# 2out_0-10V_2te.net
KiCad netlist of a schematic drawn in EAGLE
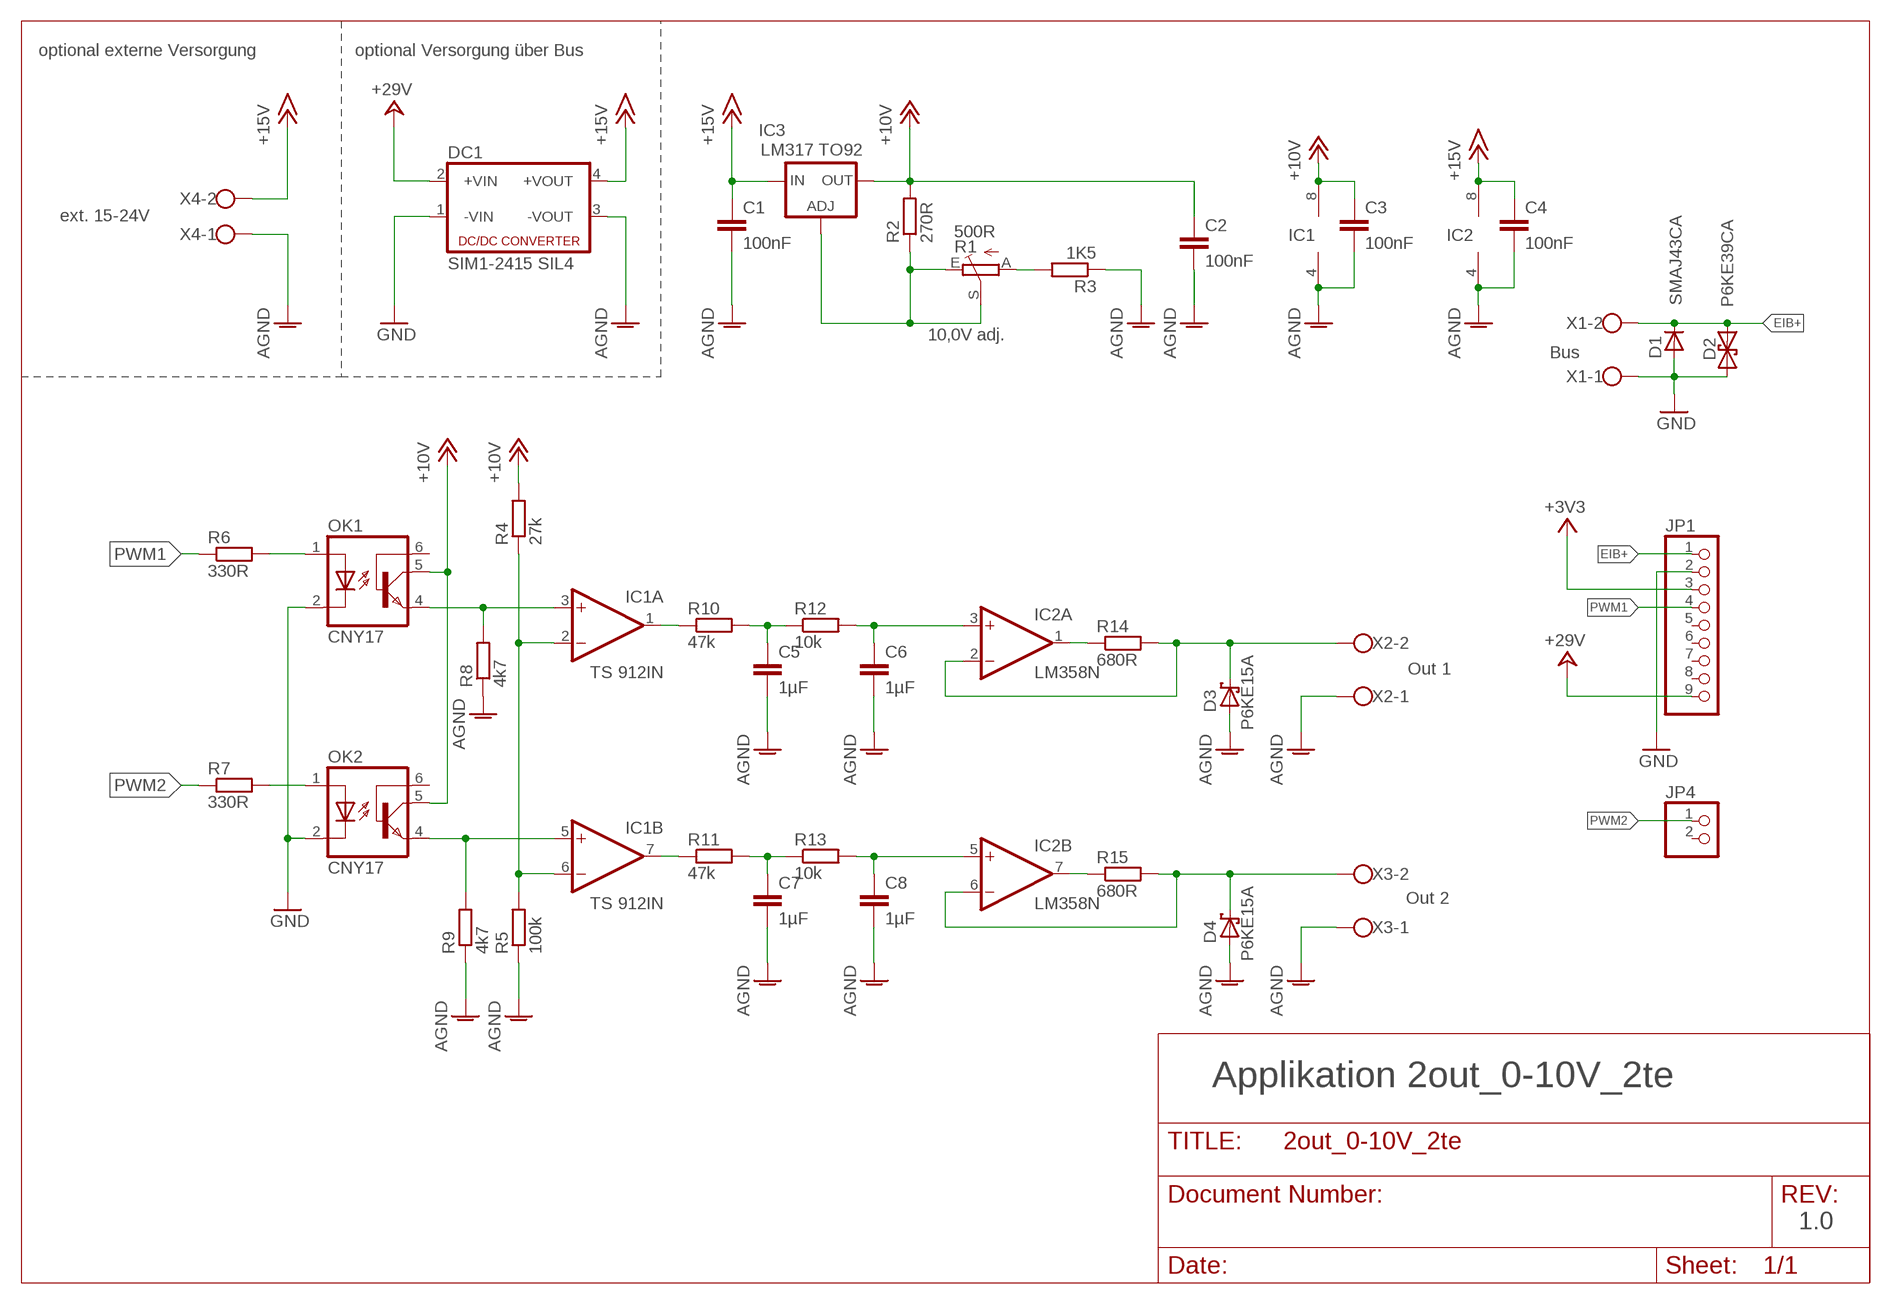
[diagram p0: schematic, sheet 1]

(export (version "E")
  (design (tool "Eeschema 10.0.6"))
  (components
    (comp (ref "C1")
      (value "100nF")
      (footprint "eagle-import:C025-024X044")
      (libsource (lib "eagle-import") (part "C-EU025-024X044"))
    )
    (comp (ref "C2")
      (value "100nF")
      (footprint "eagle-import:C025-024X044")
      (libsource (lib "eagle-import") (part "C-EU025-024X044"))
    )
    (comp (ref "C3")
      (value "100nF")
      (footprint "eagle-import:C025-024X044")
      (libsource (lib "eagle-import") (part "C-EU025-024X044"))
    )
    (comp (ref "C4")
      (value "100nF")
      (footprint "eagle-import:C025-024X044")
      (libsource (lib "eagle-import") (part "C-EU025-024X044"))
    )
    (comp (ref "C5")
      (value "1µF")
      (footprint "eagle-import:C050-024X044")
      (libsource (lib "eagle-import") (part "C-EU050-024X044"))
    )
    (comp (ref "C6")
      (value "1µF")
      (footprint "eagle-import:C050-024X044")
      (libsource (lib "eagle-import") (part "C-EU050-024X044"))
    )
    (comp (ref "C7")
      (value "1µF")
      (footprint "eagle-import:C050-024X044")
      (libsource (lib "eagle-import") (part "C-EU050-024X044"))
    )
    (comp (ref "C8")
      (value "1µF")
      (footprint "eagle-import:C050-024X044")
      (libsource (lib "eagle-import") (part "C-EU050-024X044"))
    )
    (comp (ref "D1")
      (value "SMAJ43CA")
      (footprint "eagle-import:SOD87")
      (libsource (lib "eagle-import") (part "D-SOD-87"))
    )
    (comp (ref "D2")
      (value "P6KE39CA")
      (footprint "eagle-import:DO41-7")
      (libsource (lib "eagle-import") (part "P6KEXXCDO41-7"))
    )
    (comp (ref "D3")
      (value "P6KE15A")
      (footprint "eagle-import:DO41-7")
      (libsource (lib "eagle-import") (part "P6KEXXADO41-7"))
    )
    (comp (ref "D4")
      (value "P6KE15A")
      (footprint "eagle-import:DO41-7")
      (libsource (lib "eagle-import") (part "P6KEXXADO41-7"))
    )
    (comp (ref "DC1")
      (value "SIM1-2415 SIL4")
      (footprint "eagle-import:NME")
      (libsource (lib "eagle-import") (part "NME"))
    )
    (comp (ref "IC1")
      (value "TS 912IN")
      (footprint "eagle-import:DIL08")
      (libsource (lib "eagle-import") (part "LM358N"))
    )
    (comp (ref "IC2")
      (value "LM358N")
      (footprint "eagle-import:DIL08")
      (libsource (lib "eagle-import") (part "LM358N"))
    )
    (comp (ref "IC3")
      (value "LM317 TO92")
      (footprint "eagle-import:317L")
      (libsource (lib "eagle-import") (part "LM317L"))
    )
    (comp (ref "JP1")
      (value "PINHD-1X9")
      (footprint "eagle-import:1X09")
      (libsource (lib "eagle-import") (part "PINHD-1X9"))
    )
    (comp (ref "JP4")
      (value "PINHD-1X2")
      (footprint "eagle-import:1X02")
      (libsource (lib "eagle-import") (part "PINHD-1X2"))
    )
    (comp (ref "OK1")
      (value "CNY17")
      (footprint "eagle-import:DIL06")
      (fields (field (name "MPN") "CNY17-1"))
      (libsource (lib "eagle-import") (part "CNY17"))
    )
    (comp (ref "OK2")
      (value "CNY17")
      (footprint "eagle-import:DIL06")
      (fields (field (name "MPN") "CNY17-1"))
      (libsource (lib "eagle-import") (part "CNY17"))
    )
    (comp (ref "R1")
      (value "500R")
      (footprint "eagle-import:B64W")
      (libsource (lib "eagle-import") (part "TRIM_EU-B64W"))
    )
    (comp (ref "R2")
      (value "270R")
      (footprint "eagle-import:0207_7")
      (libsource (lib "eagle-import") (part "R-EU_0207/7"))
    )
    (comp (ref "R3")
      (value "1K5")
      (footprint "eagle-import:0207_7")
      (libsource (lib "eagle-import") (part "R-EU_0207/7"))
    )
    (comp (ref "R4")
      (value "27k")
      (footprint "eagle-import:0207_7")
      (libsource (lib "eagle-import") (part "R-EU_0207/7"))
    )
    (comp (ref "R5")
      (value "100k")
      (footprint "eagle-import:0207_7")
      (libsource (lib "eagle-import") (part "R-EU_0207/7"))
    )
    (comp (ref "R6")
      (value "330R")
      (footprint "eagle-import:0207_7")
      (libsource (lib "eagle-import") (part "R-EU_0207/7"))
    )
    (comp (ref "R7")
      (value "330R")
      (footprint "eagle-import:0207_7")
      (libsource (lib "eagle-import") (part "R-EU_0207/7"))
    )
    (comp (ref "R8")
      (value "4k7")
      (footprint "eagle-import:0207_7")
      (libsource (lib "eagle-import") (part "R-EU_0207/7"))
    )
    (comp (ref "R9")
      (value "4k7")
      (footprint "eagle-import:0207_7")
      (libsource (lib "eagle-import") (part "R-EU_0207/7"))
    )
    (comp (ref "R10")
      (value "47k")
      (footprint "eagle-import:0207_7")
      (libsource (lib "eagle-import") (part "R-EU_0207/7"))
    )
    (comp (ref "R11")
      (value "47k")
      (footprint "eagle-import:0207_7")
      (libsource (lib "eagle-import") (part "R-EU_0207/7"))
    )
    (comp (ref "R12")
      (value "10k")
      (footprint "eagle-import:0207_7")
      (libsource (lib "eagle-import") (part "R-EU_0207/7"))
    )
    (comp (ref "R13")
      (value "10k")
      (footprint "eagle-import:0207_7")
      (libsource (lib "eagle-import") (part "R-EU_0207/7"))
    )
    (comp (ref "R14")
      (value "680R")
      (footprint "eagle-import:0207_7")
      (libsource (lib "eagle-import") (part "R-EU_0207/7"))
    )
    (comp (ref "R15")
      (value "680R")
      (footprint "eagle-import:0207_7")
      (libsource (lib "eagle-import") (part "R-EU_0207/7"))
    )
    (comp (ref "X1")
      (value "W237-02P")
      (footprint "eagle-import:W237-132")
      (libsource (lib "eagle-import") (part "W237-02P"))
    )
    (comp (ref "X2")
      (value "W237-02P")
      (footprint "eagle-import:W237-132")
      (libsource (lib "eagle-import") (part "W237-02P"))
    )
    (comp (ref "X3")
      (value "W237-02P")
      (footprint "eagle-import:W237-132")
      (libsource (lib "eagle-import") (part "W237-02P"))
    )
    (comp (ref "X4")
      (value "W237-02P")
      (footprint "eagle-import:W237-132")
      (libsource (lib "eagle-import") (part "W237-02P"))
    )
  )
  (nets
    (net (code "1") (name "+3V3") (class "Default")
      (node (ref "JP1") (pin "3") (pinfunction "3_3") (pintype "passive"))
    )
    (net (code "2") (name "+10V") (class "Default")
      (node (ref "C2") (pin "1") (pinfunction "1_1") (pintype "passive"))
      (node (ref "C3") (pin "1") (pinfunction "1_1") (pintype "passive"))
      (node (ref "IC1") (pin "8") (pinfunction "V+_8") (pintype "power_in"))
      (node (ref "IC3") (pin "2") (pinfunction "OUT_2") (pintype "passive"))
      (node (ref "OK1") (pin "5") (pinfunction "COL_5") (pintype "passive"))
      (node (ref "OK2") (pin "5") (pinfunction "COL_5") (pintype "passive"))
      (node (ref "R2") (pin "2") (pinfunction "2_2") (pintype "passive"))
      (node (ref "R4") (pin "2") (pinfunction "2_2") (pintype "passive"))
    )
    (net (code "3") (name "+15V") (class "Default")
      (node (ref "C1") (pin "1") (pinfunction "1_1") (pintype "passive"))
      (node (ref "C4") (pin "1") (pinfunction "1_1") (pintype "passive"))
      (node (ref "DC1") (pin "4") (pinfunction "+VOUT_4") (pintype "passive"))
      (node (ref "IC2") (pin "8") (pinfunction "V+_8") (pintype "power_in"))
      (node (ref "IC3") (pin "3") (pinfunction "IN_3") (pintype "input"))
      (node (ref "X4") (pin "2") (pinfunction "KL_2") (pintype "passive"))
    )
    (net (code "4") (name "+29V") (class "Default")
      (node (ref "DC1") (pin "2") (pinfunction "+VIN_2") (pintype "passive"))
      (node (ref "JP1") (pin "9") (pinfunction "9_9") (pintype "passive"))
    )
    (net (code "5") (name "AGND") (class "Default")
      (node (ref "C1") (pin "2") (pinfunction "2_2") (pintype "passive"))
      (node (ref "C2") (pin "2") (pinfunction "2_2") (pintype "passive"))
      (node (ref "C3") (pin "2") (pinfunction "2_2") (pintype "passive"))
      (node (ref "C4") (pin "2") (pinfunction "2_2") (pintype "passive"))
      (node (ref "C5") (pin "2") (pinfunction "2_2") (pintype "passive"))
      (node (ref "C6") (pin "2") (pinfunction "2_2") (pintype "passive"))
      (node (ref "C7") (pin "2") (pinfunction "2_2") (pintype "passive"))
      (node (ref "C8") (pin "2") (pinfunction "2_2") (pintype "passive"))
      (node (ref "D3") (pin "A") (pinfunction "A_A") (pintype "passive"))
      (node (ref "D4") (pin "A") (pinfunction "A_A") (pintype "passive"))
      (node (ref "DC1") (pin "3") (pinfunction "-VOUT_3") (pintype "passive"))
      (node (ref "IC1") (pin "4") (pinfunction "V-_4") (pintype "power_in"))
      (node (ref "IC2") (pin "4") (pinfunction "V-_4") (pintype "power_in"))
      (node (ref "R3") (pin "1") (pinfunction "1_1") (pintype "passive"))
      (node (ref "R5") (pin "1") (pinfunction "1_1") (pintype "passive"))
      (node (ref "R8") (pin "1") (pinfunction "1_1") (pintype "passive"))
      (node (ref "R9") (pin "1") (pinfunction "1_1") (pintype "passive"))
      (node (ref "X2") (pin "1") (pinfunction "KL_1") (pintype "passive"))
      (node (ref "X3") (pin "1") (pinfunction "KL_1") (pintype "passive"))
      (node (ref "X4") (pin "1") (pinfunction "KL_1") (pintype "passive"))
    )
    (net (code "6") (name "EIB+") (class "Default")
      (node (ref "D1") (pin "1") (pinfunction "C_1") (pintype "passive"))
      (node (ref "D2") (pin "C") (pinfunction "2_C") (pintype "passive"))
      (node (ref "JP1") (pin "1") (pinfunction "1_1") (pintype "passive"))
      (node (ref "X1") (pin "2") (pinfunction "KL_2") (pintype "passive"))
    )
    (net (code "7") (name "GND") (class "Default")
      (node (ref "D1") (pin "2") (pinfunction "A_2") (pintype "passive"))
      (node (ref "D2") (pin "A") (pinfunction "1_A") (pintype "passive"))
      (node (ref "DC1") (pin "1") (pinfunction "-VIN_1") (pintype "passive"))
      (node (ref "JP1") (pin "2") (pinfunction "2_2") (pintype "passive"))
      (node (ref "OK1") (pin "2") (pinfunction "C_2") (pintype "passive"))
      (node (ref "OK2") (pin "2") (pinfunction "C_2") (pintype "passive"))
      (node (ref "X1") (pin "1") (pinfunction "KL_1") (pintype "passive"))
    )
    (net (code "8") (name "Net-(C5-Pad1)") (class "Default")
      (node (ref "C5") (pin "1") (pinfunction "1_1") (pintype "passive"))
      (node (ref "R10") (pin "2") (pinfunction "2_2") (pintype "passive"))
      (node (ref "R12") (pin "1") (pinfunction "1_1") (pintype "passive"))
    )
    (net (code "9") (name "Net-(C7-Pad1)") (class "Default")
      (node (ref "C7") (pin "1") (pinfunction "1_1") (pintype "passive"))
      (node (ref "R11") (pin "2") (pinfunction "2_2") (pintype "passive"))
      (node (ref "R13") (pin "1") (pinfunction "1_1") (pintype "passive"))
    )
    (net (code "10") (name "Net-(IC1A-+IN)") (class "Default")
      (node (ref "IC1") (pin "3") (pinfunction "+IN_3") (pintype "input"))
      (node (ref "OK1") (pin "4") (pinfunction "EMI_4") (pintype "passive"))
      (node (ref "R8") (pin "2") (pinfunction "2_2") (pintype "passive"))
    )
    (net (code "11") (name "Net-(IC1A--IN)") (class "Default")
      (node (ref "IC1") (pin "2") (pinfunction "-IN_2") (pintype "input"))
      (node (ref "IC1") (pin "6") (pinfunction "-IN_6") (pintype "input"))
      (node (ref "R4") (pin "1") (pinfunction "1_1") (pintype "passive"))
      (node (ref "R5") (pin "2") (pinfunction "2_2") (pintype "passive"))
    )
    (net (code "12") (name "Net-(IC1A-OUT)") (class "Default")
      (node (ref "IC1") (pin "1") (pinfunction "OUT_1") (pintype "output"))
      (node (ref "R10") (pin "1") (pinfunction "1_1") (pintype "passive"))
    )
    (net (code "13") (name "Net-(IC1B-+IN)") (class "Default")
      (node (ref "IC1") (pin "5") (pinfunction "+IN_5") (pintype "input"))
      (node (ref "OK2") (pin "4") (pinfunction "EMI_4") (pintype "passive"))
      (node (ref "R9") (pin "2") (pinfunction "2_2") (pintype "passive"))
    )
    (net (code "14") (name "Net-(IC1B-OUT)") (class "Default")
      (node (ref "IC1") (pin "7") (pinfunction "OUT_7") (pintype "output"))
      (node (ref "R11") (pin "1") (pinfunction "1_1") (pintype "passive"))
    )
    (net (code "15") (name "Net-(IC2A-+IN)") (class "Default")
      (node (ref "C6") (pin "1") (pinfunction "1_1") (pintype "passive"))
      (node (ref "IC2") (pin "3") (pinfunction "+IN_3") (pintype "input"))
      (node (ref "R12") (pin "2") (pinfunction "2_2") (pintype "passive"))
    )
    (net (code "16") (name "Net-(IC2A--IN)") (class "Default")
      (node (ref "D3") (pin "C") (pinfunction "C_C") (pintype "passive"))
      (node (ref "IC2") (pin "2") (pinfunction "-IN_2") (pintype "input"))
      (node (ref "R14") (pin "2") (pinfunction "2_2") (pintype "passive"))
      (node (ref "X2") (pin "2") (pinfunction "KL_2") (pintype "passive"))
    )
    (net (code "17") (name "Net-(IC2A-OUT)") (class "Default")
      (node (ref "IC2") (pin "1") (pinfunction "OUT_1") (pintype "output"))
      (node (ref "R14") (pin "1") (pinfunction "1_1") (pintype "passive"))
    )
    (net (code "18") (name "Net-(IC2B-+IN)") (class "Default")
      (node (ref "C8") (pin "1") (pinfunction "1_1") (pintype "passive"))
      (node (ref "IC2") (pin "5") (pinfunction "+IN_5") (pintype "input"))
      (node (ref "R13") (pin "2") (pinfunction "2_2") (pintype "passive"))
    )
    (net (code "19") (name "Net-(IC2B--IN)") (class "Default")
      (node (ref "D4") (pin "C") (pinfunction "C_C") (pintype "passive"))
      (node (ref "IC2") (pin "6") (pinfunction "-IN_6") (pintype "input"))
      (node (ref "R15") (pin "2") (pinfunction "2_2") (pintype "passive"))
      (node (ref "X3") (pin "2") (pinfunction "KL_2") (pintype "passive"))
    )
    (net (code "20") (name "Net-(IC2B-OUT)") (class "Default")
      (node (ref "IC2") (pin "7") (pinfunction "OUT_7") (pintype "output"))
      (node (ref "R15") (pin "1") (pinfunction "1_1") (pintype "passive"))
    )
    (net (code "21") (name "Net-(IC3-ADJ)") (class "Default")
      (node (ref "IC3") (pin "1") (pinfunction "ADJ_1") (pintype "input"))
      (node (ref "R1") (pin "E") (pinfunction "E_E") (pintype "passive"))
      (node (ref "R1") (pin "S") (pinfunction "S_S") (pintype "passive"))
      (node (ref "R2") (pin "1") (pinfunction "1_1") (pintype "passive"))
    )
    (net (code "22") (name "Net-(OK1-A)") (class "Default")
      (node (ref "OK1") (pin "1") (pinfunction "A_1") (pintype "passive"))
      (node (ref "R6") (pin "2") (pinfunction "2_2") (pintype "passive"))
    )
    (net (code "23") (name "Net-(OK2-A)") (class "Default")
      (node (ref "OK2") (pin "1") (pinfunction "A_1") (pintype "passive"))
      (node (ref "R7") (pin "2") (pinfunction "2_2") (pintype "passive"))
    )
    (net (code "24") (name "Net-(R1-PadA)") (class "Default")
      (node (ref "R1") (pin "A") (pinfunction "A_A") (pintype "passive"))
      (node (ref "R3") (pin "2") (pinfunction "2_2") (pintype "passive"))
    )
    (net (code "25") (name "PWM1") (class "Default")
      (node (ref "JP1") (pin "4") (pinfunction "4_4") (pintype "passive"))
      (node (ref "R6") (pin "1") (pinfunction "1_1") (pintype "passive"))
    )
    (net (code "26") (name "PWM2") (class "Default")
      (node (ref "JP4") (pin "1") (pinfunction "1_1") (pintype "passive"))
      (node (ref "R7") (pin "1") (pinfunction "1_1") (pintype "passive"))
    )
    (net (code "27") (name "unconnected-(JP1-Pad5)") (class "Default")
      (node (ref "JP1") (pin "5") (pinfunction "5_5") (pintype "passive"))
    )
    (net (code "28") (name "unconnected-(JP1-Pad6)") (class "Default")
      (node (ref "JP1") (pin "6") (pinfunction "6_6") (pintype "passive"))
    )
    (net (code "29") (name "unconnected-(JP1-Pad7)") (class "Default")
      (node (ref "JP1") (pin "7") (pinfunction "7_7") (pintype "passive"))
    )
    (net (code "30") (name "unconnected-(JP1-Pad8)") (class "Default")
      (node (ref "JP1") (pin "8") (pinfunction "8_8") (pintype "passive"))
    )
    (net (code "31") (name "unconnected-(JP4-Pad2)") (class "Default")
      (node (ref "JP4") (pin "2") (pinfunction "2_2") (pintype "passive"))
    )
    (net (code "32") (name "unconnected-(OK1-BAS-Pad6)") (class "Default")
      (node (ref "OK1") (pin "6") (pinfunction "BAS_6") (pintype "passive"))
    )
    (net (code "33") (name "unconnected-(OK2-BAS-Pad6)") (class "Default")
      (node (ref "OK2") (pin "6") (pinfunction "BAS_6") (pintype "passive"))
    )
  )
)
